# Tasmodul_RasPi_LoRa.net
KiCad netlist of a schematic drawn in EAGLE
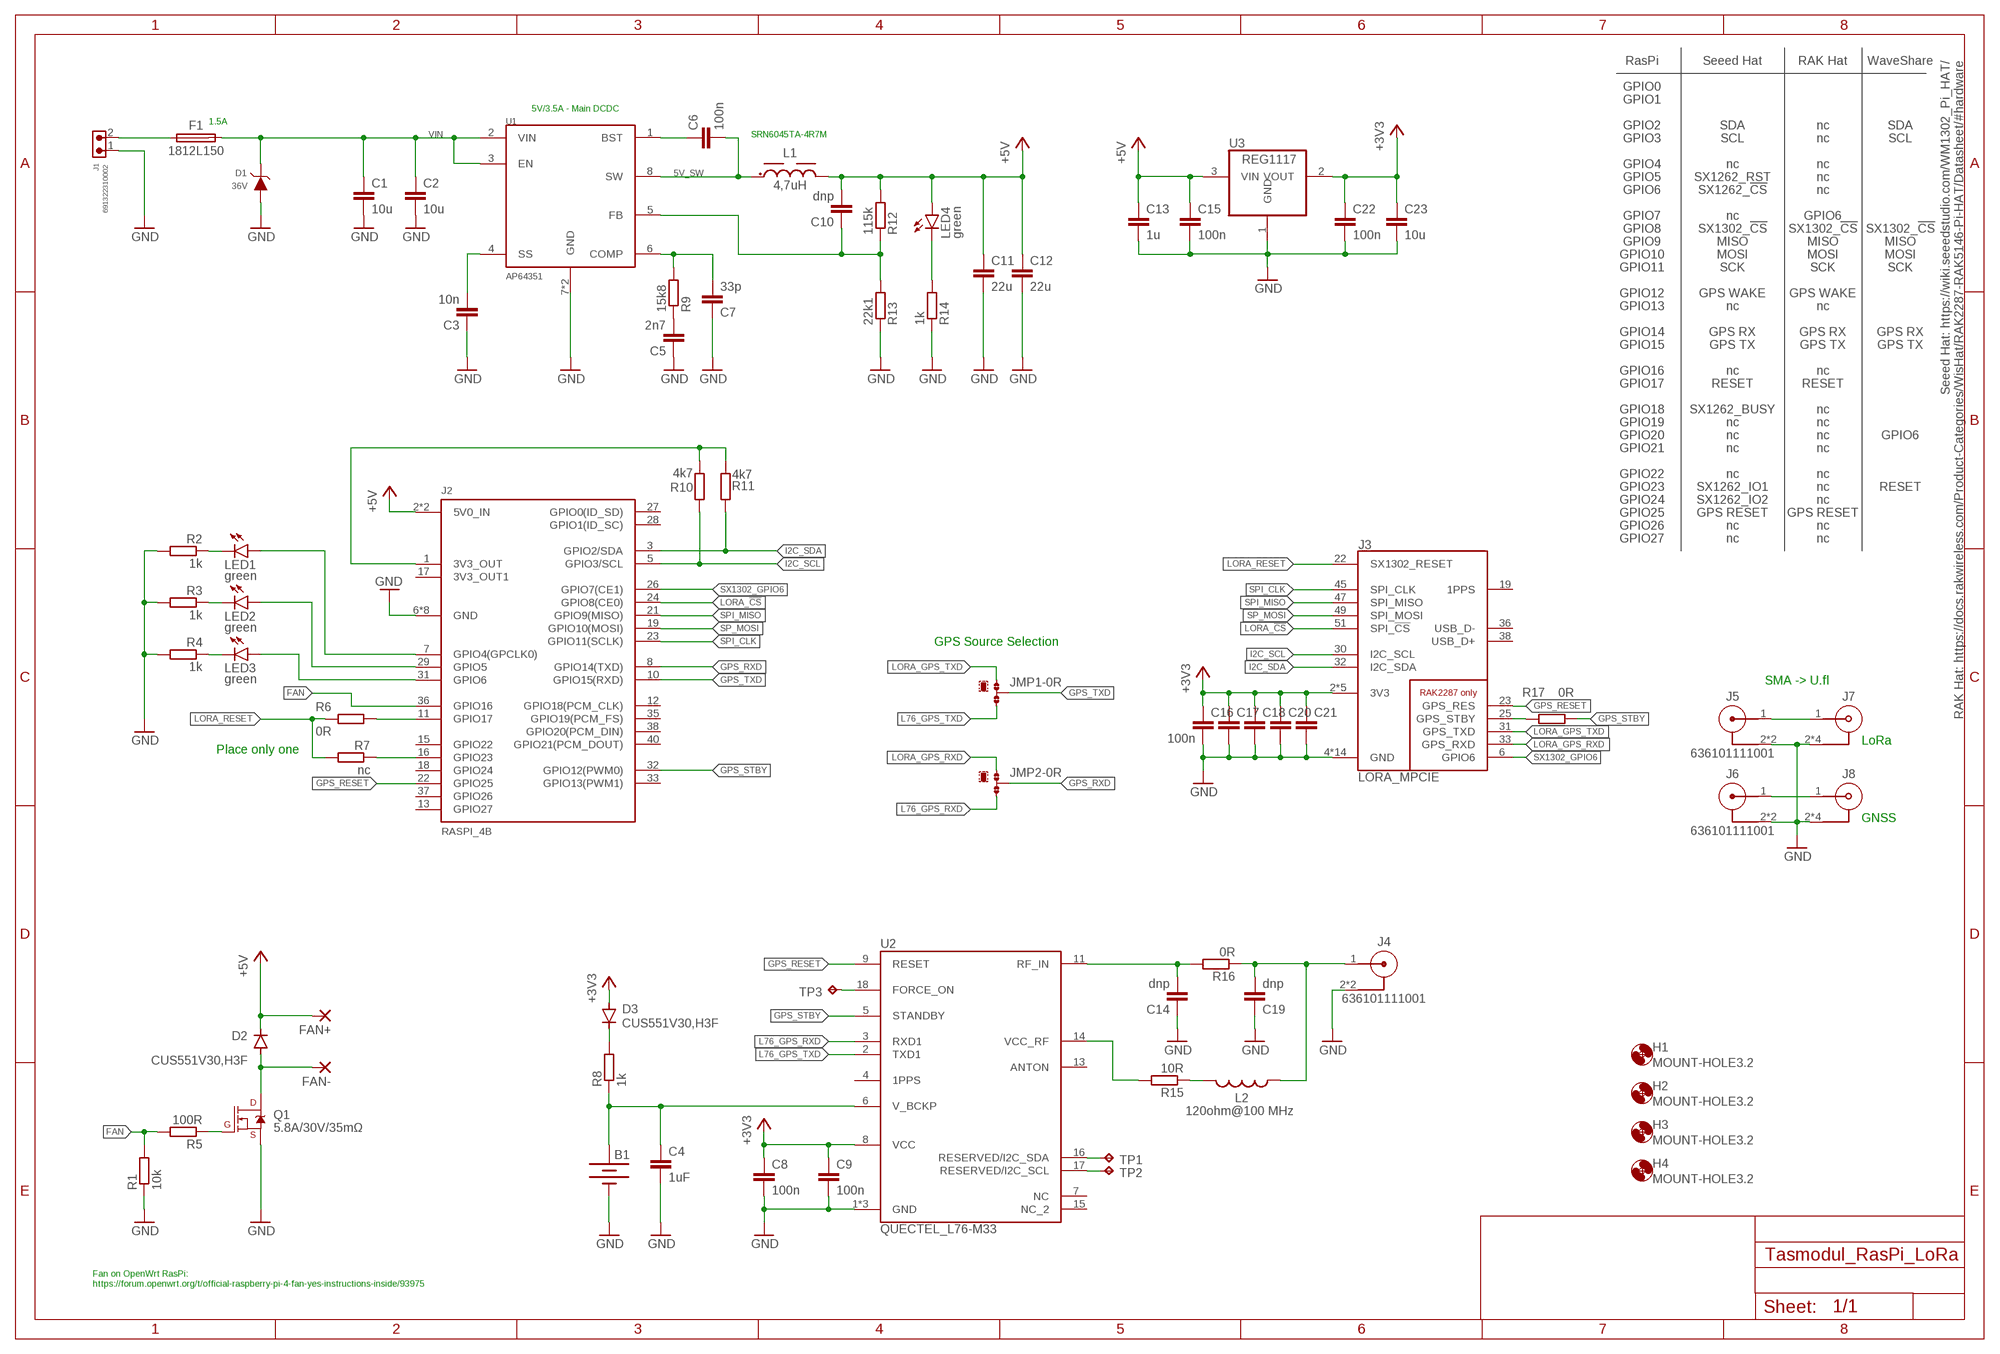
[diagram p0: schematic, sheet 1]

(export (version "E")
  (design (tool "Eeschema 10.0.6"))
  (components
    (comp (ref "B1")
      (value "6.8MM_COIN_CELL")
      (footprint "eagle-import:ML414H_IV01E")
      (libsource (lib "eagle-import") (part "ML414H_IV01E_BATTERY"))
    )
    (comp (ref "C1")
      (value "10u")
      (footprint "eagle-import:C1206")
      (libsource (lib "eagle-import") (part "C-EUC1206"))
    )
    (comp (ref "C2")
      (value "10u")
      (footprint "eagle-import:C1206")
      (libsource (lib "eagle-import") (part "C-EUC1206"))
    )
    (comp (ref "C3")
      (value "10n")
      (footprint "eagle-import:C0603")
      (libsource (lib "eagle-import") (part "C-EUC0603"))
    )
    (comp (ref "C4")
      (value "1uF")
      (footprint "eagle-import:C0603")
      (libsource (lib "eagle-import") (part "C-EUC0603"))
    )
    (comp (ref "C5")
      (value "2n7")
      (footprint "eagle-import:C0603")
      (libsource (lib "eagle-import") (part "C-EUC0603"))
    )
    (comp (ref "C6")
      (value "100n")
      (footprint "eagle-import:C0603")
      (libsource (lib "eagle-import") (part "C-EUC0603"))
    )
    (comp (ref "C7")
      (value "33p")
      (footprint "eagle-import:C0603")
      (libsource (lib "eagle-import") (part "C-EUC0603"))
    )
    (comp (ref "C8")
      (value "100n")
      (footprint "eagle-import:C0603")
      (libsource (lib "eagle-import") (part "C-EUC0603"))
    )
    (comp (ref "C9")
      (value "100n")
      (footprint "eagle-import:C0603")
      (libsource (lib "eagle-import") (part "C-EUC0603"))
    )
    (comp (ref "C10")
      (value "dnp")
      (footprint "eagle-import:C0603")
      (libsource (lib "eagle-import") (part "C-EUC0603"))
    )
    (comp (ref "C11")
      (value "22u")
      (footprint "eagle-import:C0805")
      (libsource (lib "eagle-import") (part "C-EUC0805"))
    )
    (comp (ref "C12")
      (value "22u")
      (footprint "eagle-import:C0805")
      (libsource (lib "eagle-import") (part "C-EUC0805"))
    )
    (comp (ref "C13")
      (value "1u")
      (footprint "eagle-import:C0603")
      (libsource (lib "eagle-import") (part "C-EUC0603"))
    )
    (comp (ref "C14")
      (value "dnp")
      (footprint "eagle-import:C0603")
      (libsource (lib "eagle-import") (part "C-EUC0603"))
    )
    (comp (ref "C15")
      (value "100n")
      (footprint "eagle-import:C0603")
      (libsource (lib "eagle-import") (part "C-EUC0603"))
    )
    (comp (ref "C16")
      (value "100n")
      (footprint "eagle-import:C0603")
      (libsource (lib "eagle-import") (part "C-EUC0603"))
    )
    (comp (ref "C17")
      (value "100n")
      (footprint "eagle-import:C0603")
      (libsource (lib "eagle-import") (part "C-EUC0603"))
    )
    (comp (ref "C18")
      (value "100n")
      (footprint "eagle-import:C0603")
      (libsource (lib "eagle-import") (part "C-EUC0603"))
    )
    (comp (ref "C19")
      (value "dnp")
      (footprint "eagle-import:C0603")
      (libsource (lib "eagle-import") (part "C-EUC0603"))
    )
    (comp (ref "C20")
      (value "100n")
      (footprint "eagle-import:C0603")
      (libsource (lib "eagle-import") (part "C-EUC0603"))
    )
    (comp (ref "C21")
      (value "100n")
      (footprint "eagle-import:C0603")
      (libsource (lib "eagle-import") (part "C-EUC0603"))
    )
    (comp (ref "C22")
      (value "100n")
      (footprint "eagle-import:C0603")
      (libsource (lib "eagle-import") (part "C-EUC0603"))
    )
    (comp (ref "C23")
      (value "10u")
      (footprint "eagle-import:C0603")
      (libsource (lib "eagle-import") (part "C-EUC0603"))
    )
    (comp (ref "D1")
      (value "36V")
      (footprint "eagle-import:WE-TVSP_DO-214AC_UNIDIRECTIONAL")
      (libsource (lib "eagle-import") (part "WE-TVSP_DO-214AC_400W_UNI_824500361"))
    )
    (comp (ref "D2")
      (value "CUS551V30,H3F")
      (footprint "eagle-import:SOD323-R")
      (libsource (lib "eagle-import") (part "DIODE-SOD323-R"))
    )
    (comp (ref "D3")
      (value "CUS551V30,H3F")
      (footprint "eagle-import:SOD323-R")
      (libsource (lib "eagle-import") (part "DIODE-SOD323-R"))
    )
    (comp (ref "F1")
      (value "1812L150")
      (footprint "eagle-import:FUSC4532X125")
      (fields (field (name "MANUFACTURER") "Littlefuse"))
      (libsource (lib "eagle-import") (part "1812L150"))
    )
    (comp (ref "FAN+")
      (value "1,6/0,8")
      (footprint "eagle-import:1,6_0,8")
      (libsource (lib "eagle-import") (part "1,6/0,8"))
    )
    (comp (ref "FAN-")
      (value "1,6/0,8")
      (footprint "eagle-import:1,6_0,8")
      (libsource (lib "eagle-import") (part "1,6/0,8"))
    )
    (comp (ref "H1")
      (value "MOUNT-HOLE3.2")
      (footprint "eagle-import:3,2")
      (libsource (lib "eagle-import") (part "MOUNT-HOLE3.2"))
    )
    (comp (ref "H2")
      (value "MOUNT-HOLE3.2")
      (footprint "eagle-import:3,2")
      (libsource (lib "eagle-import") (part "MOUNT-HOLE3.2"))
    )
    (comp (ref "H3")
      (value "MOUNT-HOLE3.2")
      (footprint "eagle-import:3,2")
      (libsource (lib "eagle-import") (part "MOUNT-HOLE3.2"))
    )
    (comp (ref "H4")
      (value "MOUNT-HOLE3.2")
      (footprint "eagle-import:3,2")
      (libsource (lib "eagle-import") (part "MOUNT-HOLE3.2"))
    )
    (comp (ref "J1")
      (value "691322310002")
      (footprint "eagle-import:691322310002")
      (libsource (lib "eagle-import") (part "691322310002"))
    )
    (comp (ref "J2")
      (value "RASPI_4B")
      (footprint "eagle-import:RASPI_4B_FLIPPED_SMD")
      (libsource (lib "eagle-import") (part "RASPI_4B"))
    )
    (comp (ref "J3")
      (value "LORA_MPCIE")
      (footprint "eagle-import:MINI_PCIE_CONNECTOR_5.2H")
      (libsource (lib "eagle-import") (part "LORA_MPCIE"))
    )
    (comp (ref "J4")
      (value "636101111001")
      (footprint "eagle-import:636101111001")
      (libsource (lib "eagle-import") (part "636101111001"))
    )
    (comp (ref "J5")
      (value "636101111001")
      (footprint "eagle-import:636101111001")
      (libsource (lib "eagle-import") (part "636101111001"))
    )
    (comp (ref "J6")
      (value "636101111001")
      (footprint "eagle-import:636101111001")
      (libsource (lib "eagle-import") (part "636101111001"))
    )
    (comp (ref "J7")
      (value "60311002111526")
      (footprint "eagle-import:60311002111526")
      (libsource (lib "eagle-import") (part "60311002111526"))
    )
    (comp (ref "J8")
      (value "60311002111526")
      (footprint "eagle-import:60311002111526")
      (libsource (lib "eagle-import") (part "60311002111526"))
    )
    (comp (ref "JMP1")
      (value "0R-JUMPA")
      (footprint "eagle-import:A0R-JMP")
      (libsource (lib "eagle-import") (part "0R-JUMPA"))
    )
    (comp (ref "JMP2")
      (value "0R-JUMPA")
      (footprint "eagle-import:A0R-JMP")
      (libsource (lib "eagle-import") (part "0R-JUMPA"))
    )
    (comp (ref "L1")
      (value "4,7uH")
      (footprint "eagle-import:WE-LQS_6045")
      (libsource (lib "eagle-import") (part "WE-LQS_6045_74404064033"))
    )
    (comp (ref "L2")
      (value "120ohm@100 MHz")
      (footprint "eagle-import:WE-CBF_0603_W2.2")
      (libsource (lib "eagle-import") (part "WE-CBF_0603_WB_HS_74279262"))
    )
    (comp (ref "LED1")
      (value "green")
      (footprint "eagle-import:CHIPLED_0603")
      (libsource (lib "eagle-import") (part "LEDCHIPLED_0603"))
    )
    (comp (ref "LED2")
      (value "green")
      (footprint "eagle-import:CHIPLED_0603")
      (libsource (lib "eagle-import") (part "LEDCHIPLED_0603"))
    )
    (comp (ref "LED3")
      (value "green")
      (footprint "eagle-import:CHIPLED_0603")
      (libsource (lib "eagle-import") (part "LEDCHIPLED_0603"))
    )
    (comp (ref "LED4")
      (value "green")
      (footprint "eagle-import:CHIPLED_0603")
      (libsource (lib "eagle-import") (part "LEDCHIPLED_0603"))
    )
    (comp (ref "Q1")
      (value "5.8A/30V/35mΩ")
      (footprint "eagle-import:SOT23-3")
      (libsource (lib "eagle-import") (part "MOSFET-NCH-AO3404A"))
    )
    (comp (ref "R1")
      (value "10k")
      (footprint "eagle-import:R0603")
      (libsource (lib "eagle-import") (part "R-EU_R0603"))
    )
    (comp (ref "R2")
      (value "1k")
      (footprint "eagle-import:R0603")
      (libsource (lib "eagle-import") (part "R-EU_R0603"))
    )
    (comp (ref "R3")
      (value "1k")
      (footprint "eagle-import:R0603")
      (libsource (lib "eagle-import") (part "R-EU_R0603"))
    )
    (comp (ref "R4")
      (value "1k")
      (footprint "eagle-import:R0603")
      (libsource (lib "eagle-import") (part "R-EU_R0603"))
    )
    (comp (ref "R5")
      (value "100R")
      (footprint "eagle-import:R0603")
      (libsource (lib "eagle-import") (part "R-EU_R0603"))
    )
    (comp (ref "R6")
      (value "0R")
      (footprint "eagle-import:R0603")
      (libsource (lib "eagle-import") (part "R-EU_R0603"))
    )
    (comp (ref "R7")
      (value "nc")
      (footprint "eagle-import:R0603")
      (libsource (lib "eagle-import") (part "R-EU_R0603"))
    )
    (comp (ref "R8")
      (value "1k")
      (footprint "eagle-import:R0603")
      (libsource (lib "eagle-import") (part "R-EU_R0603"))
    )
    (comp (ref "R9")
      (value "15k8")
      (footprint "eagle-import:R0603")
      (libsource (lib "eagle-import") (part "R-EU_R0603"))
    )
    (comp (ref "R10")
      (value "4k7")
      (footprint "eagle-import:R0603")
      (libsource (lib "eagle-import") (part "R-EU_R0603"))
    )
    (comp (ref "R11")
      (value "4k7")
      (footprint "eagle-import:R0603")
      (libsource (lib "eagle-import") (part "R-EU_R0603"))
    )
    (comp (ref "R12")
      (value "115k")
      (footprint "eagle-import:R0603")
      (libsource (lib "eagle-import") (part "R-EU_R0603"))
    )
    (comp (ref "R13")
      (value "22k1")
      (footprint "eagle-import:R0603")
      (libsource (lib "eagle-import") (part "R-EU_R0603"))
    )
    (comp (ref "R14")
      (value "1k")
      (footprint "eagle-import:R0603")
      (libsource (lib "eagle-import") (part "R-EU_R0603"))
    )
    (comp (ref "R15")
      (value "10R")
      (footprint "eagle-import:R0603")
      (libsource (lib "eagle-import") (part "R-EU_R0603"))
    )
    (comp (ref "R16")
      (value "0R")
      (footprint "eagle-import:R0603")
      (libsource (lib "eagle-import") (part "R-EU_R0603"))
    )
    (comp (ref "R17")
      (value "0R")
      (footprint "eagle-import:R0603")
      (libsource (lib "eagle-import") (part "R-EU_R0603"))
    )
    (comp (ref "TP1")
      (value "TPTP15R")
      (footprint "eagle-import:TP15R")
      (libsource (lib "eagle-import") (part "TPTP15R"))
    )
    (comp (ref "TP2")
      (value "TPTP15R")
      (footprint "eagle-import:TP15R")
      (libsource (lib "eagle-import") (part "TPTP15R"))
    )
    (comp (ref "TP3")
      (value "TPTP15R")
      (footprint "eagle-import:TP15R")
      (libsource (lib "eagle-import") (part "TPTP15R"))
    )
    (comp (ref "U1")
      (value "AP64351")
      (footprint "eagle-import:SOIC8-EP")
      (libsource (lib "eagle-import") (part "AP64351"))
    )
    (comp (ref "U2")
      (value "QUECTEL_L76-M33")
      (footprint "eagle-import:L76_QWS")
      (libsource (lib "eagle-import") (part "QUECTEL_L76-M33"))
    )
    (comp (ref "U3")
      (value "REG1117")
      (footprint "eagle-import:SOT223")
      (libsource (lib "eagle-import") (part "REG1117"))
    )
  )
  (nets
    (net (code "1") (name "+3V3") (class "Default")
      (node (ref "C16") (pin "1") (pinfunction "1_1") (pintype "passive"))
      (node (ref "C17") (pin "1") (pinfunction "1_1") (pintype "passive"))
      (node (ref "C18") (pin "1") (pinfunction "1_1") (pintype "passive"))
      (node (ref "C20") (pin "1") (pinfunction "1_1") (pintype "passive"))
      (node (ref "C21") (pin "1") (pinfunction "1_1") (pintype "passive"))
      (node (ref "C22") (pin "1") (pinfunction "1_1") (pintype "passive"))
      (node (ref "C23") (pin "1") (pinfunction "1_1") (pintype "passive"))
      (node (ref "C8") (pin "1") (pinfunction "1_1") (pintype "passive"))
      (node (ref "C9") (pin "1") (pinfunction "1_1") (pintype "passive"))
      (node (ref "D3") (pin "A") (pinfunction "A_A") (pintype "passive"))
      (node (ref "J3") (pin "2") (pinfunction "3V3_2") (pintype "bidirectional"))
      (node (ref "J3") (pin "24") (pinfunction "3V3_24") (pintype "bidirectional"))
      (node (ref "J3") (pin "39") (pinfunction "3V3_39") (pintype "bidirectional"))
      (node (ref "J3") (pin "41") (pinfunction "3V3_41") (pintype "bidirectional"))
      (node (ref "J3") (pin "52") (pinfunction "3V3_52") (pintype "bidirectional"))
      (node (ref "U2") (pin "8") (pinfunction "VCC_8") (pintype "power_in"))
      (node (ref "U3") (pin "2") (pinfunction "VOUT_2") (pintype "output"))
    )
    (net (code "2") (name "+5V") (class "Default")
      (node (ref "C10") (pin "2") (pinfunction "2_2") (pintype "passive"))
      (node (ref "C11") (pin "1") (pinfunction "1_1") (pintype "passive"))
      (node (ref "C12") (pin "1") (pinfunction "1_1") (pintype "passive"))
      (node (ref "C13") (pin "1") (pinfunction "1_1") (pintype "passive"))
      (node (ref "C15") (pin "1") (pinfunction "1_1") (pintype "passive"))
      (node (ref "D2") (pin "C") (pinfunction "C_C") (pintype "passive"))
      (node (ref "FAN+") (pin "1") (pinfunction "P_1") (pintype "passive"))
      (node (ref "J2") (pin "2") (pinfunction "5V0_IN_2") (pintype "bidirectional"))
      (node (ref "J2") (pin "4") (pinfunction "5V0_IN_4") (pintype "bidirectional"))
      (node (ref "L1") (pin "2") (pinfunction "2_2") (pintype "passive"))
      (node (ref "LED4") (pin "A") (pinfunction "A_A") (pintype "passive"))
      (node (ref "R12") (pin "2") (pinfunction "2_2") (pintype "passive"))
      (node (ref "U3") (pin "3") (pinfunction "VIN_3") (pintype "input"))
    )
    (net (code "3") (name "/5V_SW") (class "Default")
      (node (ref "C6") (pin "2") (pinfunction "2_2") (pintype "passive"))
      (node (ref "L1") (pin "1") (pinfunction "1_1") (pintype "passive"))
      (node (ref "U1") (pin "8") (pinfunction "SW_8") (pintype "bidirectional"))
    )
    (net (code "4") (name "/LORA_~{CS}") (class "Default")
      (node (ref "J2") (pin "24") (pinfunction "GPIO8(CE0)_24") (pintype "bidirectional"))
      (node (ref "J3") (pin "51") (pinfunction "SPI_~{CS}_51") (pintype "bidirectional"))
    )
    (net (code "5") (name "/VIN") (class "Default")
      (node (ref "C1") (pin "1") (pinfunction "1_1") (pintype "passive"))
      (node (ref "C2") (pin "1") (pinfunction "1_1") (pintype "passive"))
      (node (ref "D1") (pin "1") (pinfunction "C_1") (pintype "passive"))
      (node (ref "F1") (pin "2") (pinfunction "2_2") (pintype "passive"))
      (node (ref "U1") (pin "2") (pinfunction "VIN_2") (pintype "bidirectional"))
      (node (ref "U1") (pin "3") (pinfunction "EN_3") (pintype "bidirectional"))
    )
    (net (code "6") (name "FAN") (class "Default")
      (node (ref "J2") (pin "36") (pinfunction "GPIO16_36") (pintype "bidirectional"))
      (node (ref "R1") (pin "2") (pinfunction "2_2") (pintype "passive"))
      (node (ref "R5") (pin "2") (pinfunction "2_2") (pintype "passive"))
    )
    (net (code "7") (name "GND") (class "Default")
      (node (ref "B1") (pin "-") (pinfunction "-_-") (pintype "power_in"))
      (node (ref "C1") (pin "2") (pinfunction "2_2") (pintype "passive"))
      (node (ref "C11") (pin "2") (pinfunction "2_2") (pintype "passive"))
      (node (ref "C12") (pin "2") (pinfunction "2_2") (pintype "passive"))
      (node (ref "C13") (pin "2") (pinfunction "2_2") (pintype "passive"))
      (node (ref "C14") (pin "1") (pinfunction "1_1") (pintype "passive"))
      (node (ref "C15") (pin "2") (pinfunction "2_2") (pintype "passive"))
      (node (ref "C16") (pin "2") (pinfunction "2_2") (pintype "passive"))
      (node (ref "C17") (pin "2") (pinfunction "2_2") (pintype "passive"))
      (node (ref "C18") (pin "2") (pinfunction "2_2") (pintype "passive"))
      (node (ref "C19") (pin "1") (pinfunction "1_1") (pintype "passive"))
      (node (ref "C2") (pin "2") (pinfunction "2_2") (pintype "passive"))
      (node (ref "C20") (pin "2") (pinfunction "2_2") (pintype "passive"))
      (node (ref "C21") (pin "2") (pinfunction "2_2") (pintype "passive"))
      (node (ref "C22") (pin "2") (pinfunction "2_2") (pintype "passive"))
      (node (ref "C23") (pin "2") (pinfunction "2_2") (pintype "passive"))
      (node (ref "C3") (pin "1") (pinfunction "1_1") (pintype "passive"))
      (node (ref "C4") (pin "2") (pinfunction "2_2") (pintype "passive"))
      (node (ref "C5") (pin "1") (pinfunction "1_1") (pintype "passive"))
      (node (ref "C7") (pin "1") (pinfunction "1_1") (pintype "passive"))
      (node (ref "C8") (pin "2") (pinfunction "2_2") (pintype "passive"))
      (node (ref "C9") (pin "2") (pinfunction "2_2") (pintype "passive"))
      (node (ref "D1") (pin "2") (pinfunction "A_2") (pintype "passive"))
      (node (ref "J1") (pin "1") (pinfunction "1_1") (pintype "passive"))
      (node (ref "J2") (pin "14") (pinfunction "GND_14") (pintype "bidirectional"))
      (node (ref "J2") (pin "20") (pinfunction "GND_20") (pintype "bidirectional"))
      (node (ref "J2") (pin "25") (pinfunction "GND_25") (pintype "bidirectional"))
      (node (ref "J2") (pin "30") (pinfunction "GND_30") (pintype "bidirectional"))
      (node (ref "J2") (pin "34") (pinfunction "GND_34") (pintype "bidirectional"))
      (node (ref "J2") (pin "39") (pinfunction "GND_39") (pintype "bidirectional"))
      (node (ref "J2") (pin "6") (pinfunction "GND_6") (pintype "bidirectional"))
      (node (ref "J2") (pin "9") (pinfunction "GND_9") (pintype "bidirectional"))
      (node (ref "J3") (pin "15") (pinfunction "GND_15") (pintype "bidirectional"))
      (node (ref "J3") (pin "18") (pinfunction "GND_18") (pintype "bidirectional"))
      (node (ref "J3") (pin "21") (pinfunction "GND_21") (pintype "bidirectional"))
      (node (ref "J3") (pin "26") (pinfunction "GND_26") (pintype "bidirectional"))
      (node (ref "J3") (pin "27") (pinfunction "GND_27") (pintype "bidirectional"))
      (node (ref "J3") (pin "29") (pinfunction "GND_29") (pintype "bidirectional"))
      (node (ref "J3") (pin "34") (pinfunction "GND_34") (pintype "bidirectional"))
      (node (ref "J3") (pin "35") (pinfunction "GND_35") (pintype "bidirectional"))
      (node (ref "J3") (pin "37") (pinfunction "GND_37") (pintype "bidirectional"))
      (node (ref "J3") (pin "4") (pinfunction "GND_4") (pintype "bidirectional"))
      (node (ref "J3") (pin "40") (pinfunction "GND_40") (pintype "bidirectional"))
      (node (ref "J3") (pin "43") (pinfunction "GND_43") (pintype "bidirectional"))
      (node (ref "J3") (pin "50") (pinfunction "GND_50") (pintype "bidirectional"))
      (node (ref "J3") (pin "9") (pinfunction "GND_9") (pintype "bidirectional"))
      (node (ref "J4") (pin "2") (pinfunction "2_2") (pintype "passive"))
      (node (ref "J4") (pin "3") (pinfunction "2_3") (pintype "passive"))
      (node (ref "J5") (pin "2") (pinfunction "2_2") (pintype "passive"))
      (node (ref "J5") (pin "3") (pinfunction "2_3") (pintype "passive"))
      (node (ref "J6") (pin "2") (pinfunction "2_2") (pintype "passive"))
      (node (ref "J6") (pin "3") (pinfunction "2_3") (pintype "passive"))
      (node (ref "J7") (pin "2") (pinfunction "2_2") (pintype "passive"))
      (node (ref "J7") (pin "3") (pinfunction "2_3") (pintype "passive"))
      (node (ref "J7") (pin "4") (pinfunction "2_4") (pintype "passive"))
      (node (ref "J7") (pin "5") (pinfunction "2_5") (pintype "passive"))
      (node (ref "J8") (pin "2") (pinfunction "2_2") (pintype "passive"))
      (node (ref "J8") (pin "3") (pinfunction "2_3") (pintype "passive"))
      (node (ref "J8") (pin "4") (pinfunction "2_4") (pintype "passive"))
      (node (ref "J8") (pin "5") (pinfunction "2_5") (pintype "passive"))
      (node (ref "Q1") (pin "2") (pinfunction "S_2") (pintype "bidirectional"))
      (node (ref "R1") (pin "1") (pinfunction "1_1") (pintype "passive"))
      (node (ref "R13") (pin "1") (pinfunction "1_1") (pintype "passive"))
      (node (ref "R14") (pin "1") (pinfunction "1_1") (pintype "passive"))
      (node (ref "R2") (pin "2") (pinfunction "2_2") (pintype "passive"))
      (node (ref "R3") (pin "2") (pinfunction "2_2") (pintype "passive"))
      (node (ref "R4") (pin "2") (pinfunction "2_2") (pintype "passive"))
      (node (ref "U1") (pin "7") (pinfunction "GND_7") (pintype "bidirectional"))
      (node (ref "U1") (pin "9") (pinfunction "GND_9") (pintype "bidirectional"))
      (node (ref "U2") (pin "1") (pinfunction "GND_1") (pintype "passive"))
      (node (ref "U2") (pin "10") (pinfunction "GND_10") (pintype "passive"))
      (node (ref "U2") (pin "12") (pinfunction "GND_12") (pintype "passive"))
      (node (ref "U3") (pin "1") (pinfunction "GND_1") (pintype "power_in"))
    )
    (net (code "8") (name "GPS_RESET") (class "Default")
      (node (ref "J2") (pin "22") (pinfunction "GPIO25_22") (pintype "bidirectional"))
      (node (ref "J3") (pin "23") (pinfunction "GPS_RES_23") (pintype "bidirectional"))
      (node (ref "U2") (pin "9") (pinfunction "RESET_9") (pintype "input"))
    )
    (net (code "9") (name "GPS_RXD") (class "Default")
      (node (ref "J2") (pin "8") (pinfunction "GPIO14(TXD)_8") (pintype "bidirectional"))
      (node (ref "JMP2") (pin "2") (pinfunction "2_2") (pintype "passive"))
    )
    (net (code "10") (name "GPS_STBY") (class "Default")
      (node (ref "J2") (pin "32") (pinfunction "GPIO12(PWM0)_32") (pintype "bidirectional"))
      (node (ref "R17") (pin "1") (pinfunction "1_1") (pintype "passive"))
      (node (ref "U2") (pin "5") (pinfunction "STANDBY_5") (pintype "input"))
    )
    (net (code "11") (name "GPS_TXD") (class "Default")
      (node (ref "J2") (pin "10") (pinfunction "GPIO15(RXD)_10") (pintype "bidirectional"))
      (node (ref "JMP1") (pin "2") (pinfunction "2_2") (pintype "passive"))
    )
    (net (code "12") (name "I2C_SCL") (class "Default")
      (node (ref "J2") (pin "5") (pinfunction "GPIO3/SCL_5") (pintype "bidirectional"))
      (node (ref "J3") (pin "30") (pinfunction "I2C_SCL_30") (pintype "bidirectional"))
      (node (ref "R10") (pin "1") (pinfunction "1_1") (pintype "passive"))
    )
    (net (code "13") (name "I2C_SDA") (class "Default")
      (node (ref "J2") (pin "3") (pinfunction "GPIO2/SDA_3") (pintype "bidirectional"))
      (node (ref "J3") (pin "32") (pinfunction "I2C_SDA_32") (pintype "bidirectional"))
      (node (ref "R11") (pin "1") (pinfunction "1_1") (pintype "passive"))
    )
    (net (code "14") (name "L76_GPS_RXD") (class "Default")
      (node (ref "JMP2") (pin "3") (pinfunction "3_3") (pintype "passive"))
      (node (ref "U2") (pin "3") (pinfunction "RXD1_3") (pintype "input"))
    )
    (net (code "15") (name "L76_GPS_TXD") (class "Default")
      (node (ref "JMP1") (pin "3") (pinfunction "3_3") (pintype "passive"))
      (node (ref "U2") (pin "2") (pinfunction "TXD1_2") (pintype "output"))
    )
    (net (code "16") (name "LORA_GPS_RXD") (class "Default")
      (node (ref "J3") (pin "33") (pinfunction "GPS_RXD_33") (pintype "bidirectional"))
      (node (ref "JMP2") (pin "1") (pinfunction "1_1") (pintype "passive"))
    )
    (net (code "17") (name "LORA_GPS_TXD") (class "Default")
      (node (ref "J3") (pin "31") (pinfunction "GPS_TXD_31") (pintype "bidirectional"))
      (node (ref "JMP1") (pin "1") (pinfunction "1_1") (pintype "passive"))
    )
    (net (code "18") (name "LORA_RESET") (class "Default")
      (node (ref "J3") (pin "22") (pinfunction "SX1302_RESET_22") (pintype "bidirectional"))
      (node (ref "R6") (pin "2") (pinfunction "2_2") (pintype "passive"))
      (node (ref "R7") (pin "2") (pinfunction "2_2") (pintype "passive"))
    )
    (net (code "19") (name "Net-(C5-Pad2)") (class "Default")
      (node (ref "C5") (pin "2") (pinfunction "2_2") (pintype "passive"))
      (node (ref "R9") (pin "1") (pinfunction "1_1") (pintype "passive"))
    )
    (net (code "20") (name "Net-(C19-Pad2)") (class "Default")
      (node (ref "C19") (pin "2") (pinfunction "2_2") (pintype "passive"))
      (node (ref "J4") (pin "1") (pinfunction "1_1") (pintype "passive"))
      (node (ref "L2") (pin "1") (pinfunction "1_1") (pintype "passive"))
      (node (ref "R16") (pin "1") (pinfunction "1_1") (pintype "passive"))
    )
    (net (code "21") (name "Net-(D3-PadC)") (class "Default")
      (node (ref "D3") (pin "C") (pinfunction "C_C") (pintype "passive"))
      (node (ref "R8") (pin "2") (pinfunction "2_2") (pintype "passive"))
    )
    (net (code "22") (name "Net-(F1-Pad1)") (class "Default")
      (node (ref "F1") (pin "1") (pinfunction "1_1") (pintype "passive"))
      (node (ref "J1") (pin "2") (pinfunction "2_2") (pintype "passive"))
    )
    (net (code "23") (name "Net-(FAN--P)") (class "Default")
      (node (ref "D2") (pin "A") (pinfunction "A_A") (pintype "passive"))
      (node (ref "FAN-") (pin "1") (pinfunction "P_1") (pintype "passive"))
      (node (ref "Q1") (pin "3") (pinfunction "D_3") (pintype "bidirectional"))
    )
    (net (code "24") (name "Net-(J2-3V3_OUT)") (class "Default")
      (node (ref "J2") (pin "1") (pinfunction "3V3_OUT_1") (pintype "bidirectional"))
      (node (ref "R10") (pin "2") (pinfunction "2_2") (pintype "passive"))
      (node (ref "R11") (pin "2") (pinfunction "2_2") (pintype "passive"))
    )
    (net (code "25") (name "Net-(J2-GPIO4(GPCLK0))") (class "Default")
      (node (ref "J2") (pin "7") (pinfunction "GPIO4(GPCLK0)_7") (pintype "bidirectional"))
      (node (ref "LED1") (pin "A") (pinfunction "A_A") (pintype "passive"))
    )
    (net (code "26") (name "Net-(J2-GPIO5)") (class "Default")
      (node (ref "J2") (pin "29") (pinfunction "GPIO5_29") (pintype "bidirectional"))
      (node (ref "LED2") (pin "A") (pinfunction "A_A") (pintype "passive"))
    )
    (net (code "27") (name "Net-(J2-GPIO6)") (class "Default")
      (node (ref "J2") (pin "31") (pinfunction "GPIO6_31") (pintype "bidirectional"))
      (node (ref "LED3") (pin "A") (pinfunction "A_A") (pintype "passive"))
    )
    (net (code "28") (name "Net-(J2-GPIO17)") (class "Default")
      (node (ref "J2") (pin "11") (pinfunction "GPIO17_11") (pintype "bidirectional"))
      (node (ref "R6") (pin "1") (pinfunction "1_1") (pintype "passive"))
    )
    (net (code "29") (name "Net-(J2-GPIO23)") (class "Default")
      (node (ref "J2") (pin "16") (pinfunction "GPIO23_16") (pintype "bidirectional"))
      (node (ref "R7") (pin "1") (pinfunction "1_1") (pintype "passive"))
    )
    (net (code "30") (name "Net-(J3-GPS_STBY)") (class "Default")
      (node (ref "J3") (pin "25") (pinfunction "GPS_STBY_25") (pintype "bidirectional"))
      (node (ref "R17") (pin "2") (pinfunction "2_2") (pintype "passive"))
    )
    (net (code "31") (name "Net-(J5-Pad1)") (class "Default")
      (node (ref "J5") (pin "1") (pinfunction "1_1") (pintype "passive"))
      (node (ref "J7") (pin "1") (pinfunction "1_1") (pintype "passive"))
    )
    (net (code "32") (name "Net-(J6-Pad1)") (class "Default")
      (node (ref "J6") (pin "1") (pinfunction "1_1") (pintype "passive"))
      (node (ref "J8") (pin "1") (pinfunction "1_1") (pintype "passive"))
    )
    (net (code "33") (name "Net-(L2-Pad2)") (class "Default")
      (node (ref "L2") (pin "2") (pinfunction "2_2") (pintype "passive"))
      (node (ref "R15") (pin "1") (pinfunction "1_1") (pintype "passive"))
    )
    (net (code "34") (name "Net-(LED1-PadC)") (class "Default")
      (node (ref "LED1") (pin "C") (pinfunction "C_C") (pintype "passive"))
      (node (ref "R2") (pin "1") (pinfunction "1_1") (pintype "passive"))
    )
    (net (code "35") (name "Net-(LED2-PadC)") (class "Default")
      (node (ref "LED2") (pin "C") (pinfunction "C_C") (pintype "passive"))
      (node (ref "R3") (pin "1") (pinfunction "1_1") (pintype "passive"))
    )
    (net (code "36") (name "Net-(LED3-PadC)") (class "Default")
      (node (ref "LED3") (pin "C") (pinfunction "C_C") (pintype "passive"))
      (node (ref "R4") (pin "1") (pinfunction "1_1") (pintype "passive"))
    )
    (net (code "37") (name "Net-(LED4-PadC)") (class "Default")
      (node (ref "LED4") (pin "C") (pinfunction "C_C") (pintype "passive"))
      (node (ref "R14") (pin "2") (pinfunction "2_2") (pintype "passive"))
    )
    (net (code "38") (name "Net-(Q1-G)") (class "Default")
      (node (ref "Q1") (pin "1") (pinfunction "G_1") (pintype "bidirectional"))
      (node (ref "R5") (pin "1") (pinfunction "1_1") (pintype "passive"))
    )
    (net (code "39") (name "Net-(U1-BST)") (class "Default")
      (node (ref "C6") (pin "1") (pinfunction "1_1") (pintype "passive"))
      (node (ref "U1") (pin "1") (pinfunction "BST_1") (pintype "bidirectional"))
    )
    (net (code "40") (name "Net-(U1-COMP)") (class "Default")
      (node (ref "C7") (pin "2") (pinfunction "2_2") (pintype "passive"))
      (node (ref "R9") (pin "2") (pinfunction "2_2") (pintype "passive"))
      (node (ref "U1") (pin "6") (pinfunction "COMP_6") (pintype "bidirectional"))
    )
    (net (code "41") (name "Net-(U1-FB)") (class "Default")
      (node (ref "C10") (pin "1") (pinfunction "1_1") (pintype "passive"))
      (node (ref "R12") (pin "1") (pinfunction "1_1") (pintype "passive"))
      (node (ref "R13") (pin "2") (pinfunction "2_2") (pintype "passive"))
      (node (ref "U1") (pin "5") (pinfunction "FB_5") (pintype "bidirectional"))
    )
    (net (code "42") (name "Net-(U1-SS)") (class "Default")
      (node (ref "C3") (pin "2") (pinfunction "2_2") (pintype "passive"))
      (node (ref "U1") (pin "4") (pinfunction "SS_4") (pintype "bidirectional"))
    )
    (net (code "43") (name "Net-(U2-FORCE_ON)") (class "Default")
      (node (ref "TP3") (pin "TP") (pinfunction "TP_TP") (pintype "input"))
      (node (ref "U2") (pin "18") (pinfunction "FORCE_ON_18") (pintype "input"))
    )
    (net (code "44") (name "Net-(U2-RESERVED{slash}I2C_SCL)") (class "Default")
      (node (ref "TP2") (pin "TP") (pinfunction "TP_TP") (pintype "input"))
      (node (ref "U2") (pin "17") (pinfunction "RESERVED/I2C_SCL_17") (pintype "bidirectional"))
    )
    (net (code "45") (name "Net-(U2-RESERVED{slash}I2C_SDA)") (class "Default")
      (node (ref "TP1") (pin "TP") (pinfunction "TP_TP") (pintype "input"))
      (node (ref "U2") (pin "16") (pinfunction "RESERVED/I2C_SDA_16") (pintype "bidirectional"))
    )
    (net (code "46") (name "Net-(U2-RF_IN)") (class "Default")
      (node (ref "C14") (pin "2") (pinfunction "2_2") (pintype "passive"))
      (node (ref "R16") (pin "2") (pinfunction "2_2") (pintype "passive"))
      (node (ref "U2") (pin "11") (pinfunction "RF_IN_11") (pintype "input"))
    )
    (net (code "47") (name "Net-(U2-VCC_RF)") (class "Default")
      (node (ref "R15") (pin "2") (pinfunction "2_2") (pintype "passive"))
      (node (ref "U2") (pin "14") (pinfunction "VCC_RF_14") (pintype "power_in"))
    )
    (net (code "48") (name "Net-(U2-V_BCKP)") (class "Default")
      (node (ref "B1") (pin "+") (pinfunction "+_+") (pintype "power_in"))
      (node (ref "C4") (pin "1") (pinfunction "1_1") (pintype "passive"))
      (node (ref "R8") (pin "1") (pinfunction "1_1") (pintype "passive"))
      (node (ref "U2") (pin "6") (pinfunction "V_BCKP_6") (pintype "power_in"))
    )
    (net (code "49") (name "SPI_CLK") (class "Default")
      (node (ref "J2") (pin "23") (pinfunction "GPIO11(SCLK)_23") (pintype "bidirectional"))
      (node (ref "J3") (pin "45") (pinfunction "SPI_CLK_45") (pintype "bidirectional"))
    )
    (net (code "50") (name "SPI_MISO") (class "Default")
      (node (ref "J2") (pin "21") (pinfunction "GPIO9(MISO)_21") (pintype "bidirectional"))
      (node (ref "J3") (pin "47") (pinfunction "SPI_MISO_47") (pintype "bidirectional"))
    )
    (net (code "51") (name "SP_MOSI") (class "Default")
      (node (ref "J2") (pin "19") (pinfunction "GPIO10(MOSI)_19") (pintype "bidirectional"))
      (node (ref "J3") (pin "49") (pinfunction "SPI_MOSI_49") (pintype "bidirectional"))
    )
    (net (code "52") (name "SX1302_GPIO6") (class "Default")
      (node (ref "J2") (pin "26") (pinfunction "GPIO7(CE1)_26") (pintype "bidirectional"))
      (node (ref "J3") (pin "6") (pinfunction "GPIO6_6") (pintype "bidirectional"))
    )
    (net (code "53") (name "unconnected-(J2-3V3_OUT1-Pad17)") (class "Default")
      (node (ref "J2") (pin "17") (pinfunction "3V3_OUT1_17") (pintype "bidirectional"))
    )
    (net (code "54") (name "unconnected-(J2-GPIO0(ID_SD)-Pad27)") (class "Default")
      (node (ref "J2") (pin "27") (pinfunction "GPIO0(ID_SD)_27") (pintype "bidirectional"))
    )
    (net (code "55") (name "unconnected-(J2-GPIO1(ID_SC)-Pad28)") (class "Default")
      (node (ref "J2") (pin "28") (pinfunction "GPIO1(ID_SC)_28") (pintype "bidirectional"))
    )
    (net (code "56") (name "unconnected-(J2-GPIO13(PWM1)-Pad33)") (class "Default")
      (node (ref "J2") (pin "33") (pinfunction "GPIO13(PWM1)_33") (pintype "bidirectional"))
    )
    (net (code "57") (name "unconnected-(J2-GPIO18(PCM_CLK)-Pad12)") (class "Default")
      (node (ref "J2") (pin "12") (pinfunction "GPIO18(PCM_CLK)_12") (pintype "bidirectional"))
    )
    (net (code "58") (name "unconnected-(J2-GPIO19(PCM_FS)-Pad35)") (class "Default")
      (node (ref "J2") (pin "35") (pinfunction "GPIO19(PCM_FS)_35") (pintype "bidirectional"))
    )
    (net (code "59") (name "unconnected-(J2-GPIO20(PCM_DIN)-Pad38)") (class "Default")
      (node (ref "J2") (pin "38") (pinfunction "GPIO20(PCM_DIN)_38") (pintype "bidirectional"))
    )
    (net (code "60") (name "unconnected-(J2-GPIO21(PCM_DOUT)-Pad40)") (class "Default")
      (node (ref "J2") (pin "40") (pinfunction "GPIO21(PCM_DOUT)_40") (pintype "bidirectional"))
    )
    (net (code "61") (name "unconnected-(J2-GPIO22-Pad15)") (class "Default")
      (node (ref "J2") (pin "15") (pinfunction "GPIO22_15") (pintype "bidirectional"))
    )
    (net (code "62") (name "unconnected-(J2-GPIO24-Pad18)") (class "Default")
      (node (ref "J2") (pin "18") (pinfunction "GPIO24_18") (pintype "bidirectional"))
    )
    (net (code "63") (name "unconnected-(J2-GPIO26-Pad37)") (class "Default")
      (node (ref "J2") (pin "37") (pinfunction "GPIO26_37") (pintype "bidirectional"))
    )
    (net (code "64") (name "unconnected-(J2-GPIO27-Pad13)") (class "Default")
      (node (ref "J2") (pin "13") (pinfunction "GPIO27_13") (pintype "bidirectional"))
    )
    (net (code "65") (name "unconnected-(J3-1PPS-Pad19)") (class "Default")
      (node (ref "J3") (pin "19") (pinfunction "1PPS_19") (pintype "bidirectional"))
    )
    (net (code "66") (name "unconnected-(J3-USB_D+-Pad38)") (class "Default")
      (node (ref "J3") (pin "38") (pinfunction "USB_D+_38") (pintype "bidirectional"))
    )
    (net (code "67") (name "unconnected-(J3-USB_D--Pad36)") (class "Default")
      (node (ref "J3") (pin "36") (pinfunction "USB_D-_36") (pintype "bidirectional"))
    )
    (net (code "68") (name "unconnected-(U2-1PPS-Pad4)") (class "Default")
      (node (ref "U2") (pin "4") (pinfunction "1PPS_4") (pintype "output"))
    )
    (net (code "69") (name "unconnected-(U2-ANTON-Pad13)") (class "Default")
      (node (ref "U2") (pin "13") (pinfunction "ANTON_13") (pintype "output"))
    )
    (net (code "70") (name "unconnected-(U2-NC-Pad7)") (class "Default")
      (node (ref "U2") (pin "7") (pinfunction "NC_7") (pintype "no_connect"))
    )
    (net (code "71") (name "unconnected-(U2-NC_2-Pad15)") (class "Default")
      (node (ref "U2") (pin "15") (pinfunction "NC_2_15") (pintype "no_connect"))
    )
  )
)
